# toes_V1.net
KiCad netlist of a schematic drawn in EAGLE
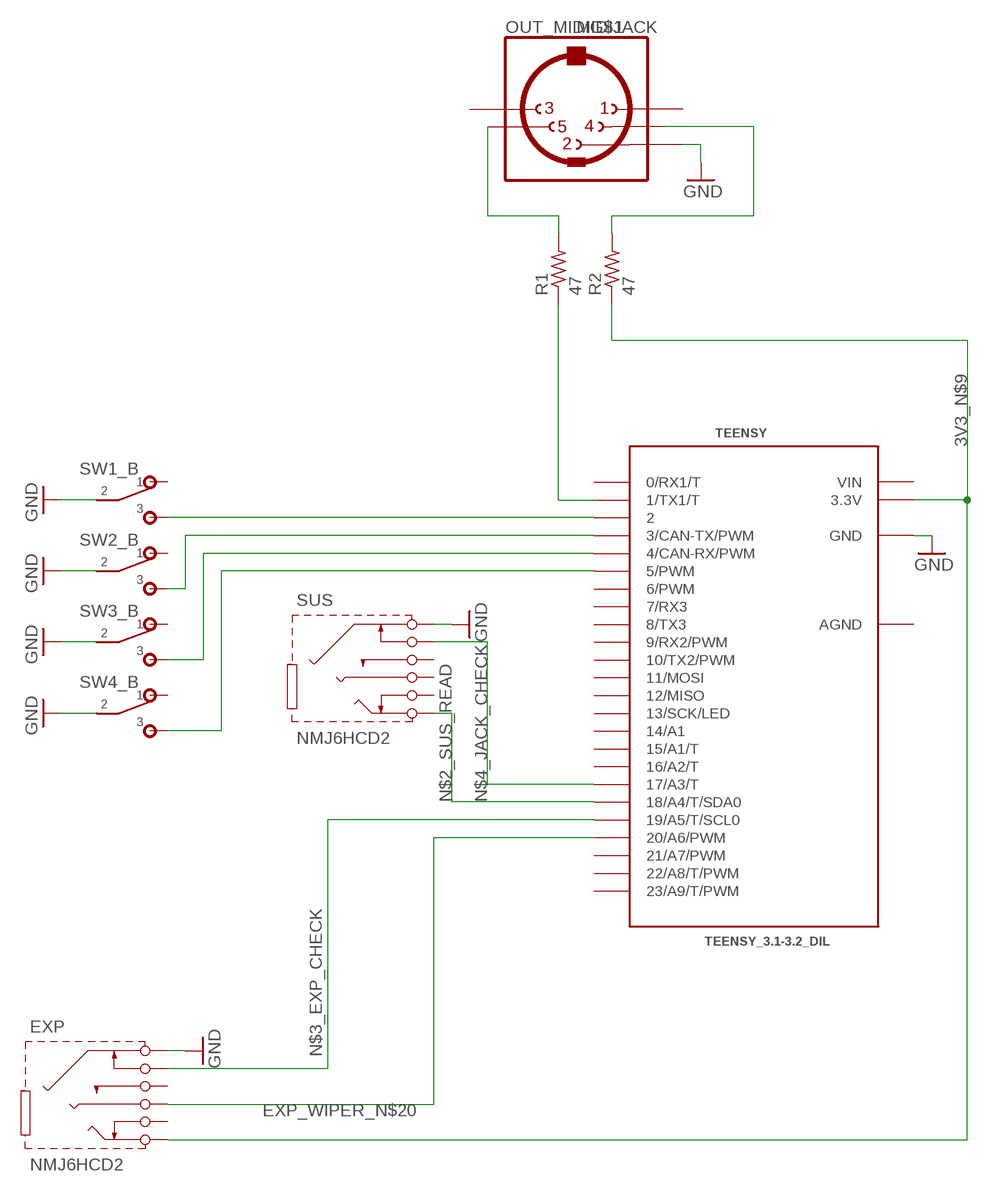
[diagram p0: schematic, sheet 1]

(export (version "E")
  (design (tool "Eeschema 10.0.6"))
  (components
    (comp (ref "EXP")
      (value "NMJ6HCD2")
      (footprint "eagle-import:NMJ6HCD2")
      (fields (field (name "MF") "Neutrik"))
      (libsource (lib "eagle-import") (part "NMJ6HCD2"))
    )
    (comp (ref "OUT_MIDI")
      (value "MIDIJACK")
      (footprint "eagle-import:CP-2350")
      (libsource (lib "eagle-import") (part "MIDIJACK"))
    )
    (comp (ref "R1")
      (value "47")
      (footprint "eagle-import:0204_7")
      (libsource (lib "eagle-import") (part "R-US_0204/7"))
    )
    (comp (ref "R2")
      (value "47")
      (footprint "eagle-import:0204_7")
      (libsource (lib "eagle-import") (part "R-US_0204/7"))
    )
    (comp (ref "SUS")
      (value "NMJ6HCD2")
      (footprint "eagle-import:NMJ6HCD2")
      (fields (field (name "MF") "Neutrik"))
      (libsource (lib "eagle-import") (part "NMJ6HCD2"))
    )
    (comp (ref "SW1")
      (value "DPDTDPDT_MOM")
      (footprint "eagle-import:SF12011F-0202-20R-M-011")
      (libsource (lib "eagle-import") (part "DPDTDPDT_MOM"))
    )
    (comp (ref "SW2")
      (value "DPDTDPDT_MOM")
      (footprint "eagle-import:SF12011F-0202-20R-M-011")
      (libsource (lib "eagle-import") (part "DPDTDPDT_MOM"))
    )
    (comp (ref "SW3")
      (value "DPDTDPDT_MOM")
      (footprint "eagle-import:SF12011F-0202-20R-M-011")
      (libsource (lib "eagle-import") (part "DPDTDPDT_MOM"))
    )
    (comp (ref "SW4")
      (value "DPDTDPDT_MOM")
      (footprint "eagle-import:SF12011F-0202-20R-M-011")
      (libsource (lib "eagle-import") (part "DPDTDPDT_MOM"))
    )
    (comp (ref "TEENSY")
      (value "TEENSY_3.1-3.2_DIL")
      (footprint "eagle-import:TEENSY_3.0-3.2&LC_DIL")
      (libsource (lib "eagle-import") (part "TEENSY_3.1-3.2_DIL"))
    )
  )
  (nets
    (net (code "1") (name "/3V3_N$9") (class "Default")
      (node (ref "EXP") (pin "T") (pinfunction "TIP_T") (pintype "passive"))
      (node (ref "R2") (pin "1") (pinfunction "1_1") (pintype "passive"))
      (node (ref "TEENSY") (pin "3.3V") (pinfunction "3.3V_3.3V") (pintype "power_in"))
    )
    (net (code "2") (name "/AGND") (class "Default")
      (node (ref "TEENSY") (pin "AGND") (pinfunction "AGND_AGND") (pintype "power_in"))
    )
    (net (code "3") (name "/EXP_WIPER_N$20") (class "Default")
      (node (ref "EXP") (pin "R") (pinfunction "RING_R") (pintype "passive"))
      (node (ref "TEENSY") (pin "20/A6") (pinfunction "20/A6/PWM_20/A6") (pintype "bidirectional"))
    )
    (net (code "4") (name "/N$2_SUS_READ") (class "Default")
      (node (ref "SUS") (pin "T") (pinfunction "TIP_T") (pintype "passive"))
      (node (ref "TEENSY") (pin "18/A4") (pinfunction "18/A4/T/SDA0_18/A4") (pintype "bidirectional"))
    )
    (net (code "5") (name "/N$3_EXP_CHECK") (class "Default")
      (node (ref "EXP") (pin "SN") (pinfunction "SLEEVE-S_SN") (pintype "passive"))
      (node (ref "TEENSY") (pin "19/A5") (pinfunction "19/A5/T/SCL0_19/A5") (pintype "bidirectional"))
    )
    (net (code "6") (name "/N$4_JACK_CHECK") (class "Default")
      (node (ref "SUS") (pin "SN") (pinfunction "SLEEVE-S_SN") (pintype "passive"))
      (node (ref "TEENSY") (pin "17/A3") (pinfunction "17/A3/T_17/A3") (pintype "bidirectional"))
    )
    (net (code "7") (name "/VIN") (class "Default")
      (node (ref "TEENSY") (pin "VIN") (pinfunction "VIN_VIN") (pintype "power_in"))
    )
    (net (code "8") (name "GND") (class "Default")
      (node (ref "EXP") (pin "S") (pinfunction "SLEEVE_S") (pintype "passive"))
      (node (ref "OUT_MIDI") (pin "2") (pinfunction "2_2") (pintype "passive"))
      (node (ref "SUS") (pin "S") (pinfunction "SLEEVE_S") (pintype "passive"))
      (node (ref "SW1") (pin "P$5") (pinfunction "2_P$5") (pintype "passive"))
      (node (ref "SW2") (pin "P$5") (pinfunction "2_P$5") (pintype "passive"))
      (node (ref "SW3") (pin "P$5") (pinfunction "2_P$5") (pintype "passive"))
      (node (ref "SW4") (pin "P$5") (pinfunction "2_P$5") (pintype "passive"))
      (node (ref "TEENSY") (pin "GND") (pinfunction "GND_GND") (pintype "power_in"))
    )
    (net (code "9") (name "Net-(OUT_MIDI-Pad4)") (class "Default")
      (node (ref "OUT_MIDI") (pin "4") (pinfunction "4_4") (pintype "passive"))
      (node (ref "R2") (pin "2") (pinfunction "2_2") (pintype "passive"))
    )
    (net (code "10") (name "Net-(OUT_MIDI-Pad5)") (class "Default")
      (node (ref "OUT_MIDI") (pin "5") (pinfunction "5_5") (pintype "passive"))
      (node (ref "R1") (pin "2") (pinfunction "2_2") (pintype "passive"))
    )
    (net (code "11") (name "Net-(SW1B-3)") (class "Default")
      (node (ref "SW1") (pin "P$6") (pinfunction "3_P$6") (pintype "passive"))
      (node (ref "TEENSY") (pin "2") (pinfunction "2_2") (pintype "bidirectional"))
    )
    (net (code "12") (name "Net-(SW2B-3)") (class "Default")
      (node (ref "SW2") (pin "P$6") (pinfunction "3_P$6") (pintype "passive"))
      (node (ref "TEENSY") (pin "3") (pinfunction "3/CAN-TX/PWM_3") (pintype "bidirectional"))
    )
    (net (code "13") (name "Net-(SW3B-3)") (class "Default")
      (node (ref "SW3") (pin "P$6") (pinfunction "3_P$6") (pintype "passive"))
      (node (ref "TEENSY") (pin "4") (pinfunction "4/CAN-RX/PWM_4") (pintype "bidirectional"))
    )
    (net (code "14") (name "Net-(SW4B-3)") (class "Default")
      (node (ref "SW4") (pin "P$6") (pinfunction "3_P$6") (pintype "passive"))
      (node (ref "TEENSY") (pin "5") (pinfunction "5/PWM_5") (pintype "bidirectional"))
    )
    (net (code "15") (name "Net-(TEENSY-1{slash}TX1{slash}T)") (class "Default")
      (node (ref "R1") (pin "1") (pinfunction "1_1") (pintype "passive"))
      (node (ref "TEENSY") (pin "1") (pinfunction "1/TX1/T_1") (pintype "bidirectional"))
    )
    (net (code "16") (name "unconnected-(EXP-RING-S-PadRN)") (class "Default")
      (node (ref "EXP") (pin "RN") (pinfunction "RING-S_RN") (pintype "passive"))
    )
    (net (code "17") (name "unconnected-(EXP-TIP-S-PadTN)") (class "Default")
      (node (ref "EXP") (pin "TN") (pinfunction "TIP-S_TN") (pintype "passive"))
    )
    (net (code "18") (name "unconnected-(OUT_MIDI-Pad1)") (class "Default")
      (node (ref "OUT_MIDI") (pin "1") (pinfunction "1_1") (pintype "passive"))
    )
    (net (code "19") (name "unconnected-(OUT_MIDI-Pad3)") (class "Default")
      (node (ref "OUT_MIDI") (pin "3") (pinfunction "3_3") (pintype "passive"))
    )
    (net (code "20") (name "unconnected-(SUS-RING-PadR)") (class "Default")
      (node (ref "SUS") (pin "R") (pinfunction "RING_R") (pintype "passive"))
    )
    (net (code "21") (name "unconnected-(SUS-RING-S-PadRN)") (class "Default")
      (node (ref "SUS") (pin "RN") (pinfunction "RING-S_RN") (pintype "passive"))
    )
    (net (code "22") (name "unconnected-(SUS-TIP-S-PadTN)") (class "Default")
      (node (ref "SUS") (pin "TN") (pinfunction "TIP-S_TN") (pintype "passive"))
    )
    (net (code "23") (name "unconnected-(SW1B-1-PadP$4)") (class "Default")
      (node (ref "SW1") (pin "P$4") (pinfunction "1_P$4") (pintype "passive"))
    )
    (net (code "24") (name "unconnected-(SW2B-1-PadP$4)") (class "Default")
      (node (ref "SW2") (pin "P$4") (pinfunction "1_P$4") (pintype "passive"))
    )
    (net (code "25") (name "unconnected-(SW3B-1-PadP$4)") (class "Default")
      (node (ref "SW3") (pin "P$4") (pinfunction "1_P$4") (pintype "passive"))
    )
    (net (code "26") (name "unconnected-(SW4B-1-PadP$4)") (class "Default")
      (node (ref "SW4") (pin "P$4") (pinfunction "1_P$4") (pintype "passive"))
    )
    (net (code "27") (name "unconnected-(TEENSY-0{slash}RX1{slash}T-Pad0)") (class "Default")
      (node (ref "TEENSY") (pin "0") (pinfunction "0/RX1/T_0") (pintype "bidirectional"))
    )
    (net (code "28") (name "unconnected-(TEENSY-6{slash}PWM-Pad6)") (class "Default")
      (node (ref "TEENSY") (pin "6") (pinfunction "6/PWM_6") (pintype "bidirectional"))
    )
    (net (code "29") (name "unconnected-(TEENSY-7{slash}RX3-Pad7)") (class "Default")
      (node (ref "TEENSY") (pin "7") (pinfunction "7/RX3_7") (pintype "bidirectional"))
    )
    (net (code "30") (name "unconnected-(TEENSY-8{slash}TX3-Pad8)") (class "Default")
      (node (ref "TEENSY") (pin "8") (pinfunction "8/TX3_8") (pintype "bidirectional"))
    )
    (net (code "31") (name "unconnected-(TEENSY-9{slash}RX2{slash}PWM-Pad9)") (class "Default")
      (node (ref "TEENSY") (pin "9") (pinfunction "9/RX2/PWM_9") (pintype "bidirectional"))
    )
    (net (code "32") (name "unconnected-(TEENSY-10{slash}TX2{slash}PWM-Pad10)") (class "Default")
      (node (ref "TEENSY") (pin "10") (pinfunction "10/TX2/PWM_10") (pintype "bidirectional"))
    )
    (net (code "33") (name "unconnected-(TEENSY-11{slash}MOSI-Pad11)") (class "Default")
      (node (ref "TEENSY") (pin "11") (pinfunction "11/MOSI_11") (pintype "bidirectional"))
    )
    (net (code "34") (name "unconnected-(TEENSY-12{slash}MISO-Pad12)") (class "Default")
      (node (ref "TEENSY") (pin "12") (pinfunction "12/MISO_12") (pintype "bidirectional"))
    )
    (net (code "35") (name "unconnected-(TEENSY-13{slash}SCK{slash}LED-Pad13)") (class "Default")
      (node (ref "TEENSY") (pin "13") (pinfunction "13/SCK/LED_13") (pintype "bidirectional"))
    )
    (net (code "36") (name "unconnected-(TEENSY-14{slash}A1-Pad14{slash}A0)") (class "Default")
      (node (ref "TEENSY") (pin "14/A0") (pinfunction "14/A1_14/A0") (pintype "bidirectional"))
    )
    (net (code "37") (name "unconnected-(TEENSY-15{slash}A1{slash}T-Pad15{slash}A1)") (class "Default")
      (node (ref "TEENSY") (pin "15/A1") (pinfunction "15/A1/T_15/A1") (pintype "bidirectional"))
    )
    (net (code "38") (name "unconnected-(TEENSY-16{slash}A2{slash}T-Pad16{slash}A2)") (class "Default")
      (node (ref "TEENSY") (pin "16/A2") (pinfunction "16/A2/T_16/A2") (pintype "bidirectional"))
    )
    (net (code "39") (name "unconnected-(TEENSY-21{slash}A7{slash}PWM-Pad21{slash}A7)") (class "Default")
      (node (ref "TEENSY") (pin "21/A7") (pinfunction "21/A7/PWM_21/A7") (pintype "bidirectional"))
    )
    (net (code "40") (name "unconnected-(TEENSY-22{slash}A8{slash}T{slash}PWM-Pad22{slash}A8)") (class "Default")
      (node (ref "TEENSY") (pin "22/A8") (pinfunction "22/A8/T/PWM_22/A8") (pintype "bidirectional"))
    )
    (net (code "41") (name "unconnected-(TEENSY-23{slash}A9{slash}T{slash}PWM-Pad23{slash}A9)") (class "Default")
      (node (ref "TEENSY") (pin "23/A9") (pinfunction "23/A9/T/PWM_23/A9") (pintype "bidirectional"))
    )
  )
)
